# schemat.net
KiCad netlist of a schematic drawn in EAGLE
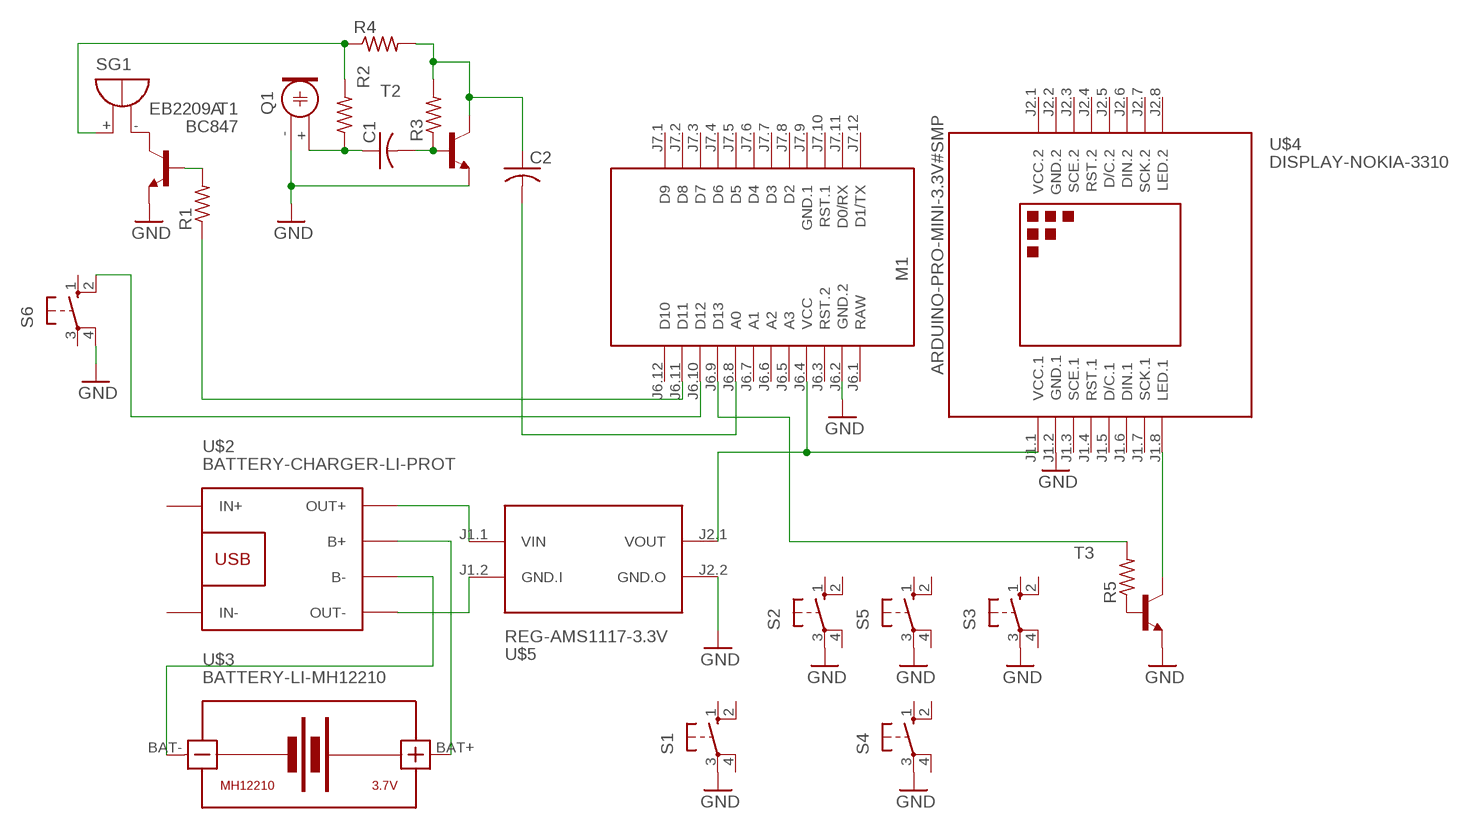
[diagram p0: schematic, sheet 1]

(export (version "E")
  (design (tool "Eeschema 10.0.6"))
  (components
    (comp (ref "C1")
      (value "C-USC2012")
      (footprint "eagle-import:C2012")
      (libsource (lib "eagle-import") (part "C-USC2012"))
    )
    (comp (ref "C2")
      (value "C-USC2012")
      (footprint "eagle-import:C2012")
      (libsource (lib "eagle-import") (part "C-USC2012"))
    )
    (comp (ref "M1")
      (value "ARDUINO-PRO-MINI-3.3V#SMP")
      (footprint "eagle-import:ARDUINO-PRO-MINI#SMP")
      (libsource (lib "eagle-import") (part "ARDUINO-PRO-MINI-#SMP3.3V"))
    )
    (comp (ref "Q1")
      (value "ELECTRET")
      (footprint "eagle-import:9.7ELECTRET")
      (libsource (lib "eagle-import") (part "ELECTRET"))
    )
    (comp (ref "R1")
      (value "R-US_R1206")
      (footprint "eagle-import:R1206")
      (libsource (lib "eagle-import") (part "R-US_R1206"))
    )
    (comp (ref "R2")
      (value "R-US_R1206")
      (footprint "eagle-import:R1206")
      (libsource (lib "eagle-import") (part "R-US_R1206"))
    )
    (comp (ref "R3")
      (value "R-US_R1206")
      (footprint "eagle-import:R1206")
      (libsource (lib "eagle-import") (part "R-US_R1206"))
    )
    (comp (ref "R4")
      (value "R-US_R1206")
      (footprint "eagle-import:R1206")
      (libsource (lib "eagle-import") (part "R-US_R1206"))
    )
    (comp (ref "R5")
      (value "R-US_R1206")
      (footprint "eagle-import:R1206")
      (libsource (lib "eagle-import") (part "R-US_R1206"))
    )
    (comp (ref "S1")
      (value "10-XX")
      (footprint "eagle-import:B3F-10XX")
      (fields (field (name "MPN") "B3F-1000"))
      (libsource (lib "eagle-import") (part "10-XX"))
    )
    (comp (ref "S2")
      (value "10-XX")
      (footprint "eagle-import:B3F-10XX")
      (fields (field (name "MPN") "B3F-1000"))
      (libsource (lib "eagle-import") (part "10-XX"))
    )
    (comp (ref "S3")
      (value "10-XX")
      (footprint "eagle-import:B3F-10XX")
      (fields (field (name "MPN") "B3F-1000"))
      (libsource (lib "eagle-import") (part "10-XX"))
    )
    (comp (ref "S4")
      (value "10-XX")
      (footprint "eagle-import:B3F-10XX")
      (fields (field (name "MPN") "B3F-1000"))
      (libsource (lib "eagle-import") (part "10-XX"))
    )
    (comp (ref "S5")
      (value "10-XX")
      (footprint "eagle-import:B3F-10XX")
      (fields (field (name "MPN") "B3F-1000"))
      (libsource (lib "eagle-import") (part "10-XX"))
    )
    (comp (ref "S6")
      (value "10-XX")
      (footprint "eagle-import:B3F-10XX")
      (fields (field (name "MPN") "B3F-1000"))
      (libsource (lib "eagle-import") (part "10-XX"))
    )
    (comp (ref "SG1")
      (value "EB2209A")
      (footprint "eagle-import:EB2209A")
      (libsource (lib "eagle-import") (part "EB2209A"))
    )
    (comp (ref "T1")
      (value "BC847")
      (footprint "eagle-import:SOT23")
      (libsource (lib "eagle-import") (part "BC847"))
    )
    (comp (ref "T2")
      (value "-NPN-SOT23-EBC")
      (footprint "eagle-import:SOT23-EBC")
      (libsource (lib "eagle-import") (part "-NPN-SOT23-EBC"))
    )
    (comp (ref "T3")
      (value "-NPN-SOT23-EBC")
      (footprint "eagle-import:SOT23-EBC")
      (libsource (lib "eagle-import") (part "-NPN-SOT23-EBC"))
    )
    (comp (ref "U$2")
      (value "BATTERY-CHARGER-LI-PROT")
      (footprint "eagle-import:BATTERY-CHARGER-LI-PROT")
      (libsource (lib "eagle-import") (part "BATTERY-CHARGER-LI-PROT"))
    )
    (comp (ref "U$3")
      (value "BATTERY-LI-MH12210")
      (footprint "eagle-import:BATTERY-LI-MH12210")
      (libsource (lib "eagle-import") (part "BATTERY-LI-MH12210"))
    )
    (comp (ref "U$4")
      (value "DISPLAY-NOKIA-3310")
      (footprint "eagle-import:DISPLAY-NOKIA-3310")
      (libsource (lib "eagle-import") (part "DISPLAY-NOKIA-3310"))
    )
    (comp (ref "U$5")
      (value "REG-AMS1117-3.3V")
      (footprint "eagle-import:REG-AMS1117")
      (libsource (lib "eagle-import") (part "REG-AMS1117-3.3V"))
    )
  )
  (nets
    (net (code "1") (name "/GND.1") (class "Default")
      (node (ref "M1") (pin "J7.9") (pinfunction "GND.1_J7.9") (pintype "power_in"))
    )
    (net (code "2") (name "/GND.2") (class "Default")
      (node (ref "U$4") (pin "J2.2") (pinfunction "GND.2_J2.2") (pintype "power_in"))
    )
    (net (code "3") (name "/RAW") (class "Default")
      (node (ref "M1") (pin "J6.1") (pinfunction "RAW_J6.1") (pintype "power_in"))
    )
    (net (code "4") (name "/VCC.2") (class "Default")
      (node (ref "U$4") (pin "J2.1") (pinfunction "VCC.2_J2.1") (pintype "power_in"))
    )
    (net (code "5") (name "GND") (class "Default")
      (node (ref "M1") (pin "J6.2") (pinfunction "GND.2_J6.2") (pintype "power_in"))
      (node (ref "Q1") (pin "-") (pinfunction "1_-") (pintype "passive"))
      (node (ref "S1") (pin "3") (pinfunction "P_3") (pintype "passive"))
      (node (ref "S2") (pin "3") (pinfunction "P_3") (pintype "passive"))
      (node (ref "S3") (pin "3") (pinfunction "P_3") (pintype "passive"))
      (node (ref "S4") (pin "3") (pinfunction "P_3") (pintype "passive"))
      (node (ref "S5") (pin "3") (pinfunction "P_3") (pintype "passive"))
      (node (ref "S6") (pin "4") (pinfunction "P1_4") (pintype "passive"))
      (node (ref "T1") (pin "2") (pinfunction "E_2") (pintype "passive"))
      (node (ref "T2") (pin "E") (pinfunction "E_E") (pintype "passive"))
      (node (ref "T3") (pin "E") (pinfunction "E_E") (pintype "passive"))
      (node (ref "U$4") (pin "J1.2") (pinfunction "GND.1_J1.2") (pintype "power_in"))
      (node (ref "U$5") (pin "J2.2") (pinfunction "GND.O_J2.2") (pintype "bidirectional"))
    )
    (net (code "6") (name "Net-(C1-Pad2)") (class "Default")
      (node (ref "C1") (pin "2") (pinfunction "2_2") (pintype "passive"))
      (node (ref "R3") (pin "1") (pinfunction "1_1") (pintype "passive"))
      (node (ref "T2") (pin "B") (pinfunction "B_B") (pintype "passive"))
    )
    (net (code "7") (name "Net-(C2-Pad1)") (class "Default")
      (node (ref "C2") (pin "1") (pinfunction "1_1") (pintype "passive"))
      (node (ref "R3") (pin "2") (pinfunction "2_2") (pintype "passive"))
      (node (ref "R4") (pin "2") (pinfunction "2_2") (pintype "passive"))
      (node (ref "T2") (pin "C") (pinfunction "C_C") (pintype "passive"))
    )
    (net (code "8") (name "Net-(M1-A0)") (class "Default")
      (node (ref "C2") (pin "2") (pinfunction "2_2") (pintype "passive"))
      (node (ref "M1") (pin "J6.8") (pinfunction "A0_J6.8") (pintype "bidirectional"))
    )
    (net (code "9") (name "Net-(M1-D11)") (class "Default")
      (node (ref "M1") (pin "J6.11") (pinfunction "D11_J6.11") (pintype "bidirectional"))
      (node (ref "R1") (pin "1") (pinfunction "1_1") (pintype "passive"))
    )
    (net (code "10") (name "Net-(M1-D12)") (class "Default")
      (node (ref "M1") (pin "J6.10") (pinfunction "D12_J6.10") (pintype "bidirectional"))
      (node (ref "S6") (pin "2") (pinfunction "S1_2") (pintype "passive"))
    )
    (net (code "11") (name "Net-(M1-D13)") (class "Default")
      (node (ref "M1") (pin "J6.9") (pinfunction "D13_J6.9") (pintype "bidirectional"))
      (node (ref "R5") (pin "2") (pinfunction "2_2") (pintype "passive"))
    )
    (net (code "12") (name "Net-(M1-VCC)") (class "Default")
      (node (ref "M1") (pin "J6.4") (pinfunction "VCC_J6.4") (pintype "power_in"))
      (node (ref "U$4") (pin "J1.1") (pinfunction "VCC.1_J1.1") (pintype "power_in"))
      (node (ref "U$5") (pin "J2.1") (pinfunction "VOUT_J2.1") (pintype "bidirectional"))
    )
    (net (code "13") (name "Net-(Q1-2)") (class "Default")
      (node (ref "C1") (pin "1") (pinfunction "1_1") (pintype "passive"))
      (node (ref "Q1") (pin "+") (pinfunction "2_+") (pintype "passive"))
      (node (ref "R2") (pin "1") (pinfunction "1_1") (pintype "passive"))
    )
    (net (code "14") (name "Net-(R2-Pad2)") (class "Default")
      (node (ref "R2") (pin "2") (pinfunction "2_2") (pintype "passive"))
      (node (ref "R4") (pin "1") (pinfunction "1_1") (pintype "passive"))
      (node (ref "SG1") (pin "+") (pinfunction "+_+") (pintype "passive"))
    )
    (net (code "15") (name "Net-(R5-Pad1)") (class "Default")
      (node (ref "R5") (pin "1") (pinfunction "1_1") (pintype "passive"))
      (node (ref "T3") (pin "B") (pinfunction "B_B") (pintype "passive"))
    )
    (net (code "16") (name "Net-(T1-B)") (class "Default")
      (node (ref "R1") (pin "2") (pinfunction "2_2") (pintype "passive"))
      (node (ref "T1") (pin "1") (pinfunction "B_1") (pintype "passive"))
    )
    (net (code "17") (name "Net-(T1-C)") (class "Default")
      (node (ref "SG1") (pin "-") (pinfunction "-_-") (pintype "passive"))
      (node (ref "T1") (pin "3") (pinfunction "C_3") (pintype "passive"))
    )
    (net (code "18") (name "Net-(U$2-PadB+)") (class "Default")
      (node (ref "U$2") (pin "B+") (pinfunction "B+_B+") (pintype "bidirectional"))
      (node (ref "U$3") (pin "BAT+") (pinfunction "BAT+_BAT+") (pintype "power_in"))
    )
    (net (code "19") (name "Net-(U$2-PadB-)") (class "Default")
      (node (ref "U$2") (pin "B-") (pinfunction "B-_B-") (pintype "bidirectional"))
      (node (ref "U$3") (pin "BAT-") (pinfunction "BAT-_BAT-") (pintype "power_in"))
    )
    (net (code "20") (name "Net-(U$4-LED.1)") (class "Default")
      (node (ref "T3") (pin "C") (pinfunction "C_C") (pintype "passive"))
      (node (ref "U$4") (pin "J1.8") (pinfunction "LED.1_J1.8") (pintype "input"))
    )
    (net (code "21") (name "Net-(U$5-GND.I)") (class "Default")
      (node (ref "U$2") (pin "OUT-") (pinfunction "OUT-_OUT-") (pintype "bidirectional"))
      (node (ref "U$5") (pin "J1.2") (pinfunction "GND.I_J1.2") (pintype "bidirectional"))
    )
    (net (code "22") (name "Net-(U$5-VIN)") (class "Default")
      (node (ref "U$2") (pin "OUT+") (pinfunction "OUT+_OUT+") (pintype "bidirectional"))
      (node (ref "U$5") (pin "J1.1") (pinfunction "VIN_J1.1") (pintype "bidirectional"))
    )
    (net (code "23") (name "unconnected-(M1-A1-PadJ6.7)") (class "Default")
      (node (ref "M1") (pin "J6.7") (pinfunction "A1_J6.7") (pintype "bidirectional"))
    )
    (net (code "24") (name "unconnected-(M1-A2-PadJ6.6)") (class "Default")
      (node (ref "M1") (pin "J6.6") (pinfunction "A2_J6.6") (pintype "bidirectional"))
    )
    (net (code "25") (name "unconnected-(M1-A3-PadJ6.5)") (class "Default")
      (node (ref "M1") (pin "J6.5") (pinfunction "A3_J6.5") (pintype "bidirectional"))
    )
    (net (code "26") (name "unconnected-(M1-D0{slash}RX-PadJ7.11)") (class "Default")
      (node (ref "M1") (pin "J7.11") (pinfunction "D0/RX_J7.11") (pintype "bidirectional"))
    )
    (net (code "27") (name "unconnected-(M1-D1{slash}TX-PadJ7.12)") (class "Default")
      (node (ref "M1") (pin "J7.12") (pinfunction "D1/TX_J7.12") (pintype "bidirectional"))
    )
    (net (code "28") (name "unconnected-(M1-D2-PadJ7.8)") (class "Default")
      (node (ref "M1") (pin "J7.8") (pinfunction "D2_J7.8") (pintype "bidirectional"))
    )
    (net (code "29") (name "unconnected-(M1-D3-PadJ7.7)") (class "Default")
      (node (ref "M1") (pin "J7.7") (pinfunction "D3_J7.7") (pintype "bidirectional"))
    )
    (net (code "30") (name "unconnected-(M1-D4-PadJ7.6)") (class "Default")
      (node (ref "M1") (pin "J7.6") (pinfunction "D4_J7.6") (pintype "bidirectional"))
    )
    (net (code "31") (name "unconnected-(M1-D5-PadJ7.5)") (class "Default")
      (node (ref "M1") (pin "J7.5") (pinfunction "D5_J7.5") (pintype "bidirectional"))
    )
    (net (code "32") (name "unconnected-(M1-D6-PadJ7.4)") (class "Default")
      (node (ref "M1") (pin "J7.4") (pinfunction "D6_J7.4") (pintype "bidirectional"))
    )
    (net (code "33") (name "unconnected-(M1-D7-PadJ7.3)") (class "Default")
      (node (ref "M1") (pin "J7.3") (pinfunction "D7_J7.3") (pintype "bidirectional"))
    )
    (net (code "34") (name "unconnected-(M1-D8-PadJ7.2)") (class "Default")
      (node (ref "M1") (pin "J7.2") (pinfunction "D8_J7.2") (pintype "bidirectional"))
    )
    (net (code "35") (name "unconnected-(M1-D9-PadJ7.1)") (class "Default")
      (node (ref "M1") (pin "J7.1") (pinfunction "D9_J7.1") (pintype "bidirectional"))
    )
    (net (code "36") (name "unconnected-(M1-D10-PadJ6.12)") (class "Default")
      (node (ref "M1") (pin "J6.12") (pinfunction "D10_J6.12") (pintype "bidirectional"))
    )
    (net (code "37") (name "unconnected-(M1-RST.1-PadJ7.10)") (class "Default")
      (node (ref "M1") (pin "J7.10") (pinfunction "RST.1_J7.10") (pintype "bidirectional"))
    )
    (net (code "38") (name "unconnected-(M1-RST.2-PadJ6.3)") (class "Default")
      (node (ref "M1") (pin "J6.3") (pinfunction "RST.2_J6.3") (pintype "bidirectional"))
    )
    (net (code "39") (name "unconnected-(S1-P1-Pad4)") (class "Default")
      (node (ref "S1") (pin "4") (pinfunction "P1_4") (pintype "passive"))
    )
    (net (code "40") (name "unconnected-(S1-S-Pad1)") (class "Default")
      (node (ref "S1") (pin "1") (pinfunction "S_1") (pintype "passive"))
    )
    (net (code "41") (name "unconnected-(S1-S1-Pad2)") (class "Default")
      (node (ref "S1") (pin "2") (pinfunction "S1_2") (pintype "passive"))
    )
    (net (code "42") (name "unconnected-(S2-P1-Pad4)") (class "Default")
      (node (ref "S2") (pin "4") (pinfunction "P1_4") (pintype "passive"))
    )
    (net (code "43") (name "unconnected-(S2-S-Pad1)") (class "Default")
      (node (ref "S2") (pin "1") (pinfunction "S_1") (pintype "passive"))
    )
    (net (code "44") (name "unconnected-(S2-S1-Pad2)") (class "Default")
      (node (ref "S2") (pin "2") (pinfunction "S1_2") (pintype "passive"))
    )
    (net (code "45") (name "unconnected-(S3-P1-Pad4)") (class "Default")
      (node (ref "S3") (pin "4") (pinfunction "P1_4") (pintype "passive"))
    )
    (net (code "46") (name "unconnected-(S3-S-Pad1)") (class "Default")
      (node (ref "S3") (pin "1") (pinfunction "S_1") (pintype "passive"))
    )
    (net (code "47") (name "unconnected-(S3-S1-Pad2)") (class "Default")
      (node (ref "S3") (pin "2") (pinfunction "S1_2") (pintype "passive"))
    )
    (net (code "48") (name "unconnected-(S4-P1-Pad4)") (class "Default")
      (node (ref "S4") (pin "4") (pinfunction "P1_4") (pintype "passive"))
    )
    (net (code "49") (name "unconnected-(S4-S-Pad1)") (class "Default")
      (node (ref "S4") (pin "1") (pinfunction "S_1") (pintype "passive"))
    )
    (net (code "50") (name "unconnected-(S4-S1-Pad2)") (class "Default")
      (node (ref "S4") (pin "2") (pinfunction "S1_2") (pintype "passive"))
    )
    (net (code "51") (name "unconnected-(S5-P1-Pad4)") (class "Default")
      (node (ref "S5") (pin "4") (pinfunction "P1_4") (pintype "passive"))
    )
    (net (code "52") (name "unconnected-(S5-S-Pad1)") (class "Default")
      (node (ref "S5") (pin "1") (pinfunction "S_1") (pintype "passive"))
    )
    (net (code "53") (name "unconnected-(S5-S1-Pad2)") (class "Default")
      (node (ref "S5") (pin "2") (pinfunction "S1_2") (pintype "passive"))
    )
    (net (code "54") (name "unconnected-(S6-P-Pad3)") (class "Default")
      (node (ref "S6") (pin "3") (pinfunction "P_3") (pintype "passive"))
    )
    (net (code "55") (name "unconnected-(S6-S-Pad1)") (class "Default")
      (node (ref "S6") (pin "1") (pinfunction "S_1") (pintype "passive"))
    )
    (net (code "56") (name "unconnected-(U$2-PadIN+)") (class "Default")
      (node (ref "U$2") (pin "IN+") (pinfunction "IN+_IN+") (pintype "bidirectional"))
    )
    (net (code "57") (name "unconnected-(U$2-PadIN-)") (class "Default")
      (node (ref "U$2") (pin "IN-") (pinfunction "IN-_IN-") (pintype "bidirectional"))
    )
    (net (code "58") (name "unconnected-(U$4-DIN.1-PadJ1.6)") (class "Default")
      (node (ref "U$4") (pin "J1.6") (pinfunction "DIN.1_J1.6") (pintype "bidirectional"))
    )
    (net (code "59") (name "unconnected-(U$4-DIN.2-PadJ2.6)") (class "Default")
      (node (ref "U$4") (pin "J2.6") (pinfunction "DIN.2_J2.6") (pintype "bidirectional"))
    )
    (net (code "60") (name "unconnected-(U$4-D{slash}C.1-PadJ1.5)") (class "Default")
      (node (ref "U$4") (pin "J1.5") (pinfunction "D/C.1_J1.5") (pintype "bidirectional"))
    )
    (net (code "61") (name "unconnected-(U$4-D{slash}C.2-PadJ2.5)") (class "Default")
      (node (ref "U$4") (pin "J2.5") (pinfunction "D/C.2_J2.5") (pintype "bidirectional"))
    )
    (net (code "62") (name "unconnected-(U$4-LED.2-PadJ2.8)") (class "Default")
      (node (ref "U$4") (pin "J2.8") (pinfunction "LED.2_J2.8") (pintype "input"))
    )
    (net (code "63") (name "unconnected-(U$4-RST.1-PadJ1.4)") (class "Default")
      (node (ref "U$4") (pin "J1.4") (pinfunction "RST.1_J1.4") (pintype "bidirectional"))
    )
    (net (code "64") (name "unconnected-(U$4-RST.2-PadJ2.4)") (class "Default")
      (node (ref "U$4") (pin "J2.4") (pinfunction "RST.2_J2.4") (pintype "bidirectional"))
    )
    (net (code "65") (name "unconnected-(U$4-SCE.1-PadJ1.3)") (class "Default")
      (node (ref "U$4") (pin "J1.3") (pinfunction "SCE.1_J1.3") (pintype "bidirectional"))
    )
    (net (code "66") (name "unconnected-(U$4-SCE.2-PadJ2.3)") (class "Default")
      (node (ref "U$4") (pin "J2.3") (pinfunction "SCE.2_J2.3") (pintype "bidirectional"))
    )
    (net (code "67") (name "unconnected-(U$4-SCK.1-PadJ1.7)") (class "Default")
      (node (ref "U$4") (pin "J1.7") (pinfunction "SCK.1_J1.7") (pintype "bidirectional"))
    )
    (net (code "68") (name "unconnected-(U$4-SCK.2-PadJ2.7)") (class "Default")
      (node (ref "U$4") (pin "J2.7") (pinfunction "SCK.2_J2.7") (pintype "bidirectional"))
    )
  )
)
